# Mic_to_pi_entire_design_without_pinouts.net
KiCad netlist of a schematic drawn in EAGLE
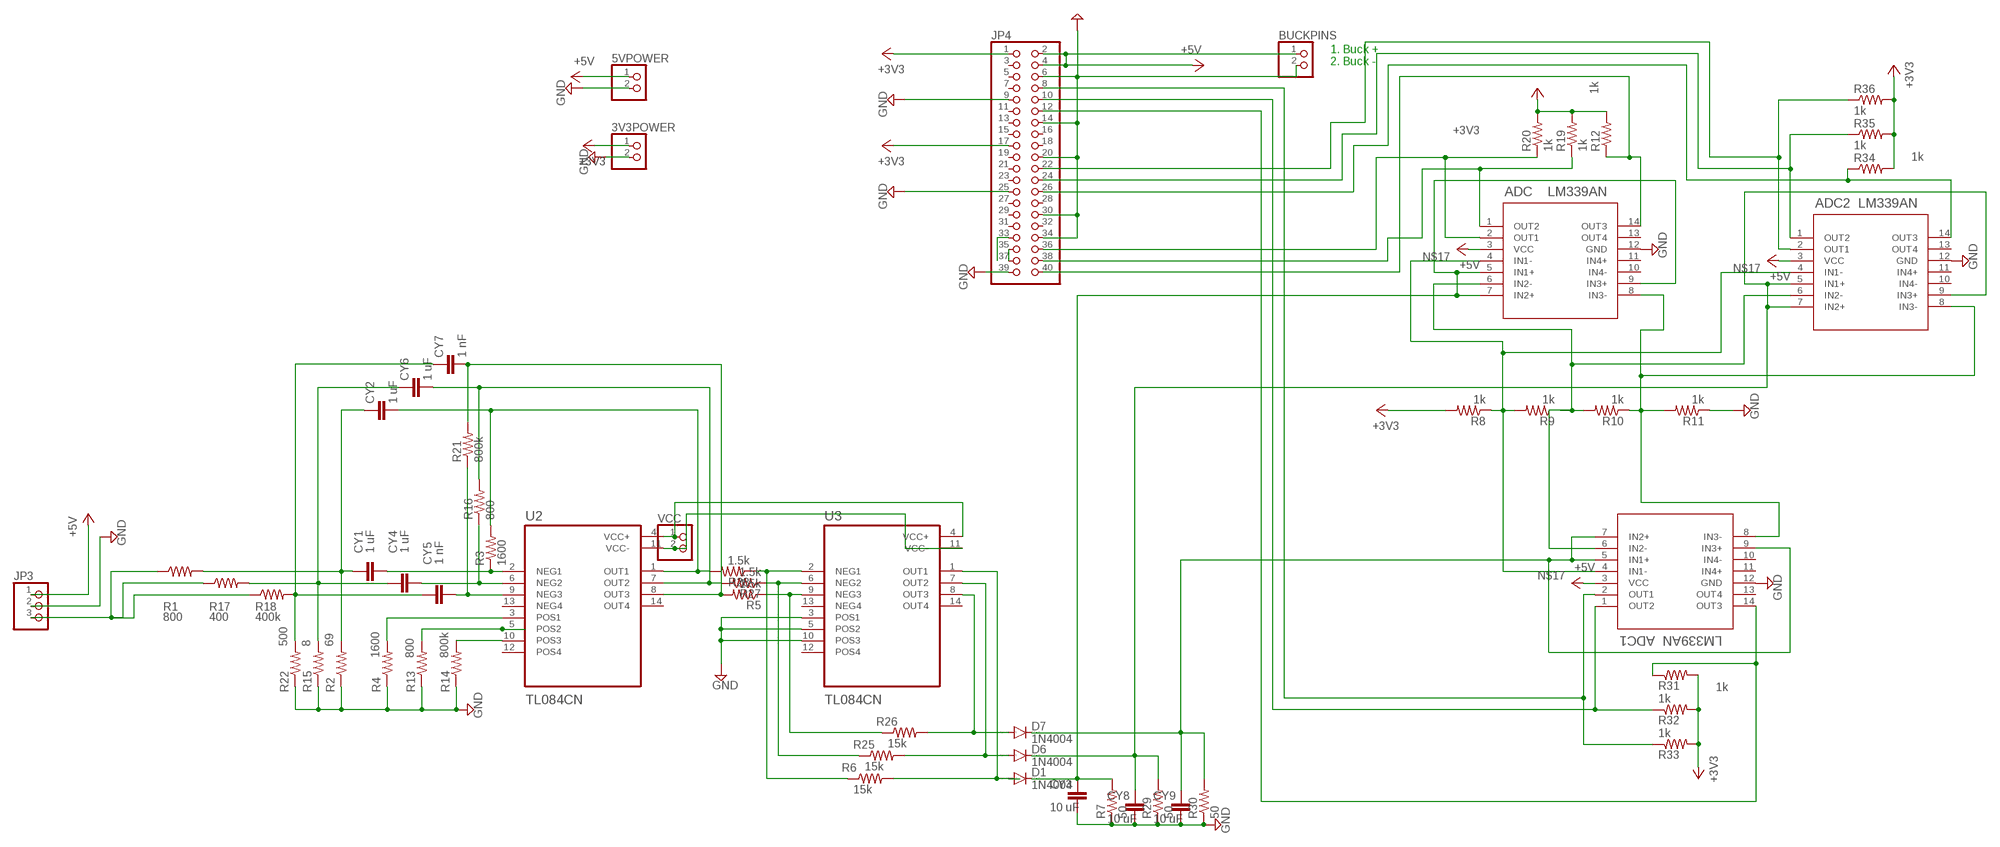
[diagram p0: schematic, sheet 1]

(export (version "E")
  (design (tool "Eeschema 10.0.6"))
  (components
    (comp (ref "3V3POWER")
      (value "PINHD-1X2")
      (footprint "eagle-import:1X02")
      (libsource (lib "eagle-import") (part "PINHD-1X2"))
    )
    (comp (ref "5VPOWER")
      (value "PINHD-1X2")
      (footprint "eagle-import:1X02")
      (libsource (lib "eagle-import") (part "PINHD-1X2"))
    )
    (comp (ref "ADC")
      (value "LM339AN")
      (footprint "eagle-import:PDIP14_646-06_ONS")
      (fields (field (name "COPYRIGHT") "Copyright (C) 2022 Ultra Librarian. All rights reserved."))
      (libsource (lib "eagle-import") (part "LM339AN"))
    )
    (comp (ref "ADC1")
      (value "LM339AN")
      (footprint "eagle-import:PDIP14_646-06_ONS")
      (fields (field (name "COPYRIGHT") "Copyright (C) 2022 Ultra Librarian. All rights reserved."))
      (libsource (lib "eagle-import") (part "LM339AN"))
    )
    (comp (ref "ADC2")
      (value "LM339AN")
      (footprint "eagle-import:PDIP14_646-06_ONS")
      (fields (field (name "COPYRIGHT") "Copyright (C) 2022 Ultra Librarian. All rights reserved."))
      (libsource (lib "eagle-import") (part "LM339AN"))
    )
    (comp (ref "BUCKPINS")
      (value "PINHD-1X2")
      (footprint "eagle-import:1X02")
      (libsource (lib "eagle-import") (part "PINHD-1X2"))
    )
    (comp (ref "CY1")
      (value "1 uF")
      (footprint "eagle-import:YC7B5")
      (libsource (lib "eagle-import") (part "CYYC7B5"))
    )
    (comp (ref "CY2")
      (value "1 uF")
      (footprint "eagle-import:YC7B5")
      (libsource (lib "eagle-import") (part "CYYC7B5"))
    )
    (comp (ref "CY3")
      (value "10 uF")
      (footprint "eagle-import:YC7B5")
      (libsource (lib "eagle-import") (part "CYYC7B5"))
    )
    (comp (ref "CY4")
      (value "1 uF")
      (footprint "eagle-import:YC7B5")
      (libsource (lib "eagle-import") (part "CYYC7B5"))
    )
    (comp (ref "CY5")
      (value "1 nF")
      (footprint "eagle-import:YC7B5")
      (libsource (lib "eagle-import") (part "CYYC7B5"))
    )
    (comp (ref "CY6")
      (value "1 uF")
      (footprint "eagle-import:YC7B5")
      (libsource (lib "eagle-import") (part "CYYC7B5"))
    )
    (comp (ref "CY7")
      (value "1 nF")
      (footprint "eagle-import:YC7B5")
      (libsource (lib "eagle-import") (part "CYYC7B5"))
    )
    (comp (ref "CY8")
      (value "10 uF")
      (footprint "eagle-import:YC7B5")
      (libsource (lib "eagle-import") (part "CYYC7B5"))
    )
    (comp (ref "CY9")
      (value "10 uF")
      (footprint "eagle-import:YC7B5")
      (libsource (lib "eagle-import") (part "CYYC7B5"))
    )
    (comp (ref "D1")
      (value "1N4004")
      (footprint "eagle-import:DO41-10")
      (libsource (lib "eagle-import") (part "1N4004"))
    )
    (comp (ref "D6")
      (value "1N4004")
      (footprint "eagle-import:DO41-10")
      (libsource (lib "eagle-import") (part "1N4004"))
    )
    (comp (ref "D7")
      (value "1N4004")
      (footprint "eagle-import:DO41-10")
      (libsource (lib "eagle-import") (part "1N4004"))
    )
    (comp (ref "JP3")
      (value "PINHD-1X3")
      (footprint "eagle-import:1X03")
      (libsource (lib "eagle-import") (part "PINHD-1X3"))
    )
    (comp (ref "JP4")
      (value "PINHD-2X20")
      (footprint "eagle-import:2X20")
      (libsource (lib "eagle-import") (part "PINHD-2X20"))
    )
    (comp (ref "R1")
      (value "800")
      (footprint "eagle-import:0204_7")
      (libsource (lib "eagle-import") (part "R-US_0204/7"))
    )
    (comp (ref "R2")
      (value "69")
      (footprint "eagle-import:0204_7")
      (libsource (lib "eagle-import") (part "R-US_0204/7"))
    )
    (comp (ref "R3")
      (value "1600")
      (footprint "eagle-import:0204_7")
      (libsource (lib "eagle-import") (part "R-US_0204/7"))
    )
    (comp (ref "R4")
      (value "1600")
      (footprint "eagle-import:0204_7")
      (libsource (lib "eagle-import") (part "R-US_0204/7"))
    )
    (comp (ref "R5")
      (value "1.5k")
      (footprint "eagle-import:0204_7")
      (libsource (lib "eagle-import") (part "R-US_0204/7"))
    )
    (comp (ref "R6")
      (value "15k")
      (footprint "eagle-import:0204_7")
      (libsource (lib "eagle-import") (part "R-US_0204/7"))
    )
    (comp (ref "R7")
      (value "50")
      (footprint "eagle-import:0204_7")
      (libsource (lib "eagle-import") (part "R-US_0204/7"))
    )
    (comp (ref "R8")
      (value "1k")
      (footprint "eagle-import:0204_7")
      (libsource (lib "eagle-import") (part "R-US_0204/7"))
    )
    (comp (ref "R9")
      (value "1k")
      (footprint "eagle-import:0207_2V")
      (libsource (lib "eagle-import") (part "R-US_0207/2V"))
    )
    (comp (ref "R10")
      (value "1k")
      (footprint "eagle-import:0207_2V")
      (libsource (lib "eagle-import") (part "R-US_0207/2V"))
    )
    (comp (ref "R11")
      (value "1k")
      (footprint "eagle-import:0207_2V")
      (libsource (lib "eagle-import") (part "R-US_0207/2V"))
    )
    (comp (ref "R12")
      (value "1k")
      (footprint "eagle-import:0207_2V")
      (libsource (lib "eagle-import") (part "R-US_0207/2V"))
    )
    (comp (ref "R13")
      (value "800")
      (footprint "eagle-import:0204_7")
      (libsource (lib "eagle-import") (part "R-US_0204/7"))
    )
    (comp (ref "R14")
      (value "800k")
      (footprint "eagle-import:0204_7")
      (libsource (lib "eagle-import") (part "R-US_0204/7"))
    )
    (comp (ref "R15")
      (value "8")
      (footprint "eagle-import:0204_7")
      (libsource (lib "eagle-import") (part "R-US_0204/7"))
    )
    (comp (ref "R16")
      (value "800")
      (footprint "eagle-import:0204_7")
      (libsource (lib "eagle-import") (part "R-US_0204/7"))
    )
    (comp (ref "R17")
      (value "400")
      (footprint "eagle-import:0204_7")
      (libsource (lib "eagle-import") (part "R-US_0204/7"))
    )
    (comp (ref "R18")
      (value "400k")
      (footprint "eagle-import:0204_7")
      (libsource (lib "eagle-import") (part "R-US_0204/7"))
    )
    (comp (ref "R19")
      (value "1k")
      (footprint "eagle-import:0204_7")
      (libsource (lib "eagle-import") (part "R-US_0204/7"))
    )
    (comp (ref "R20")
      (value "1k")
      (footprint "eagle-import:0204_7")
      (libsource (lib "eagle-import") (part "R-US_0204/7"))
    )
    (comp (ref "R21")
      (value "800k")
      (footprint "eagle-import:0204_7")
      (libsource (lib "eagle-import") (part "R-US_0204/7"))
    )
    (comp (ref "R22")
      (value "500")
      (footprint "eagle-import:0204_7")
      (libsource (lib "eagle-import") (part "R-US_0204/7"))
    )
    (comp (ref "R25")
      (value "15k")
      (footprint "eagle-import:0204_7")
      (libsource (lib "eagle-import") (part "R-US_0204/7"))
    )
    (comp (ref "R26")
      (value "15k")
      (footprint "eagle-import:0204_7")
      (libsource (lib "eagle-import") (part "R-US_0204/7"))
    )
    (comp (ref "R27")
      (value "1.5k")
      (footprint "eagle-import:0204_7")
      (libsource (lib "eagle-import") (part "R-US_0204/7"))
    )
    (comp (ref "R28")
      (value "1.5k")
      (footprint "eagle-import:0204_7")
      (libsource (lib "eagle-import") (part "R-US_0204/7"))
    )
    (comp (ref "R29")
      (value "50")
      (footprint "eagle-import:0204_7")
      (libsource (lib "eagle-import") (part "R-US_0204/7"))
    )
    (comp (ref "R30")
      (value "50")
      (footprint "eagle-import:0204_7")
      (libsource (lib "eagle-import") (part "R-US_0204/7"))
    )
    (comp (ref "R31")
      (value "1k")
      (footprint "eagle-import:0207_2V")
      (libsource (lib "eagle-import") (part "R-US_0207/2V"))
    )
    (comp (ref "R32")
      (value "1k")
      (footprint "eagle-import:0204_7")
      (libsource (lib "eagle-import") (part "R-US_0204/7"))
    )
    (comp (ref "R33")
      (value "1k")
      (footprint "eagle-import:0204_7")
      (libsource (lib "eagle-import") (part "R-US_0204/7"))
    )
    (comp (ref "R34")
      (value "1k")
      (footprint "eagle-import:0207_2V")
      (libsource (lib "eagle-import") (part "R-US_0207/2V"))
    )
    (comp (ref "R35")
      (value "1k")
      (footprint "eagle-import:0204_7")
      (libsource (lib "eagle-import") (part "R-US_0204/7"))
    )
    (comp (ref "R36")
      (value "1k")
      (footprint "eagle-import:0204_7")
      (libsource (lib "eagle-import") (part "R-US_0204/7"))
    )
    (comp (ref "U2")
      (value "TL084CN")
      (footprint "eagle-import:DIP794W45P254L1969H508Q14")
      (fields (field (name "DIGI-KEY_PART_NUMBER") "296-1784-5-ND") (field (name "MF") "Texas Instruments"))
      (libsource (lib "eagle-import") (part "TL084CN"))
    )
    (comp (ref "U3")
      (value "TL084CN")
      (footprint "eagle-import:DIP794W45P254L1969H508Q14")
      (fields (field (name "DIGI-KEY_PART_NUMBER") "296-1784-5-ND") (field (name "MF") "Texas Instruments"))
      (libsource (lib "eagle-import") (part "TL084CN"))
    )
    (comp (ref "VCC")
      (value "PINHD-1X2")
      (footprint "eagle-import:1X02")
      (libsource (lib "eagle-import") (part "PINHD-1X2"))
    )
  )
  (nets
    (net (code "1") (name "+3V3") (class "Default")
      (node (ref "3V3POWER") (pin "1") (pinfunction "1_1") (pintype "passive"))
      (node (ref "JP4") (pin "1") (pinfunction "1_1") (pintype "passive"))
      (node (ref "JP4") (pin "17") (pinfunction "17_17") (pintype "passive"))
      (node (ref "R12") (pin "2") (pinfunction "2_2") (pintype "passive"))
      (node (ref "R19") (pin "2") (pinfunction "2_2") (pintype "passive"))
      (node (ref "R20") (pin "2") (pinfunction "2_2") (pintype "passive"))
      (node (ref "R31") (pin "2") (pinfunction "2_2") (pintype "passive"))
      (node (ref "R32") (pin "2") (pinfunction "2_2") (pintype "passive"))
      (node (ref "R33") (pin "2") (pinfunction "2_2") (pintype "passive"))
      (node (ref "R34") (pin "2") (pinfunction "2_2") (pintype "passive"))
      (node (ref "R35") (pin "2") (pinfunction "2_2") (pintype "passive"))
      (node (ref "R36") (pin "2") (pinfunction "2_2") (pintype "passive"))
      (node (ref "R8") (pin "2") (pinfunction "2_2") (pintype "passive"))
    )
    (net (code "2") (name "+5V") (class "Default")
      (node (ref "5VPOWER") (pin "1") (pinfunction "1_1") (pintype "passive"))
      (node (ref "ADC") (pin "3") (pinfunction "VCC_3") (pintype "power_in"))
      (node (ref "ADC1") (pin "3") (pinfunction "VCC_3") (pintype "power_in"))
      (node (ref "ADC2") (pin "3") (pinfunction "VCC_3") (pintype "power_in"))
      (node (ref "BUCKPINS") (pin "1") (pinfunction "1_1") (pintype "passive"))
      (node (ref "JP3") (pin "1") (pinfunction "1_1") (pintype "passive"))
      (node (ref "JP4") (pin "2") (pinfunction "2_2") (pintype "passive"))
      (node (ref "JP4") (pin "4") (pinfunction "4_4") (pintype "passive"))
    )
    (net (code "3") (name "/N$17") (class "Default")
      (node (ref "ADC") (pin "4") (pinfunction "IN1-_4") (pintype "input"))
      (node (ref "ADC1") (pin "4") (pinfunction "IN1-_4") (pintype "input"))
      (node (ref "ADC2") (pin "4") (pinfunction "IN1-_4") (pintype "input"))
      (node (ref "R8") (pin "1") (pinfunction "1_1") (pintype "passive"))
      (node (ref "R9") (pin "2") (pinfunction "2_2") (pintype "passive"))
    )
    (net (code "4") (name "GND") (class "Default")
      (node (ref "3V3POWER") (pin "2") (pinfunction "2_2") (pintype "passive"))
      (node (ref "5VPOWER") (pin "2") (pinfunction "2_2") (pintype "passive"))
      (node (ref "ADC") (pin "12") (pinfunction "GND_12") (pintype "passive"))
      (node (ref "ADC1") (pin "12") (pinfunction "GND_12") (pintype "passive"))
      (node (ref "ADC2") (pin "12") (pinfunction "GND_12") (pintype "passive"))
      (node (ref "BUCKPINS") (pin "2") (pinfunction "2_2") (pintype "passive"))
      (node (ref "CY3") (pin "2") (pinfunction "2_2") (pintype "passive"))
      (node (ref "CY8") (pin "2") (pinfunction "2_2") (pintype "passive"))
      (node (ref "CY9") (pin "2") (pinfunction "2_2") (pintype "passive"))
      (node (ref "JP3") (pin "2") (pinfunction "2_2") (pintype "passive"))
      (node (ref "JP4") (pin "14") (pinfunction "14_14") (pintype "passive"))
      (node (ref "JP4") (pin "20") (pinfunction "20_20") (pintype "passive"))
      (node (ref "JP4") (pin "25") (pinfunction "25_25") (pintype "passive"))
      (node (ref "JP4") (pin "30") (pinfunction "30_30") (pintype "passive"))
      (node (ref "JP4") (pin "34") (pinfunction "34_34") (pintype "passive"))
      (node (ref "JP4") (pin "39") (pinfunction "39_39") (pintype "passive"))
      (node (ref "JP4") (pin "6") (pinfunction "6_6") (pintype "passive"))
      (node (ref "JP4") (pin "9") (pinfunction "9_9") (pintype "passive"))
      (node (ref "R11") (pin "1") (pinfunction "1_1") (pintype "passive"))
      (node (ref "R13") (pin "1") (pinfunction "1_1") (pintype "passive"))
      (node (ref "R14") (pin "1") (pinfunction "1_1") (pintype "passive"))
      (node (ref "R15") (pin "1") (pinfunction "1_1") (pintype "passive"))
      (node (ref "R2") (pin "1") (pinfunction "1_1") (pintype "passive"))
      (node (ref "R22") (pin "1") (pinfunction "1_1") (pintype "passive"))
      (node (ref "R29") (pin "1") (pinfunction "1_1") (pintype "passive"))
      (node (ref "R30") (pin "1") (pinfunction "1_1") (pintype "passive"))
      (node (ref "R4") (pin "1") (pinfunction "1_1") (pintype "passive"))
      (node (ref "R7") (pin "1") (pinfunction "1_1") (pintype "passive"))
      (node (ref "U3") (pin "10") (pinfunction "POS3_10") (pintype "input"))
      (node (ref "U3") (pin "3") (pinfunction "POS1_3") (pintype "input"))
      (node (ref "U3") (pin "5") (pinfunction "POS2_5") (pintype "input"))
    )
    (net (code "5") (name "Net-(ADC-IN1+)") (class "Default")
      (node (ref "ADC") (pin "5") (pinfunction "IN1+_5") (pintype "input"))
      (node (ref "ADC") (pin "7") (pinfunction "IN2+_7") (pintype "input"))
      (node (ref "ADC") (pin "9") (pinfunction "IN3+_9") (pintype "input"))
      (node (ref "CY3") (pin "1") (pinfunction "1_1") (pintype "passive"))
      (node (ref "D1") (pin "C") (pinfunction "C_C") (pintype "passive"))
      (node (ref "R7") (pin "2") (pinfunction "2_2") (pintype "passive"))
    )
    (net (code "6") (name "Net-(ADC-IN2-)") (class "Default")
      (node (ref "ADC") (pin "6") (pinfunction "IN2-_6") (pintype "input"))
      (node (ref "ADC1") (pin "6") (pinfunction "IN2-_6") (pintype "input"))
      (node (ref "ADC2") (pin "6") (pinfunction "IN2-_6") (pintype "input"))
      (node (ref "R10") (pin "2") (pinfunction "2_2") (pintype "passive"))
      (node (ref "R9") (pin "1") (pinfunction "1_1") (pintype "passive"))
    )
    (net (code "7") (name "Net-(ADC-IN3-)") (class "Default")
      (node (ref "ADC") (pin "8") (pinfunction "IN3-_8") (pintype "input"))
      (node (ref "ADC1") (pin "8") (pinfunction "IN3-_8") (pintype "input"))
      (node (ref "ADC2") (pin "8") (pinfunction "IN3-_8") (pintype "input"))
      (node (ref "R10") (pin "1") (pinfunction "1_1") (pintype "passive"))
      (node (ref "R11") (pin "2") (pinfunction "2_2") (pintype "passive"))
    )
    (net (code "8") (name "Net-(ADC-OUT1)") (class "Default")
      (node (ref "ADC") (pin "2") (pinfunction "OUT1_2") (pintype "output"))
      (node (ref "JP4") (pin "36") (pinfunction "36_36") (pintype "passive"))
      (node (ref "R20") (pin "1") (pinfunction "1_1") (pintype "passive"))
    )
    (net (code "9") (name "Net-(ADC-OUT2)") (class "Default")
      (node (ref "ADC") (pin "1") (pinfunction "OUT2_1") (pintype "output"))
      (node (ref "JP4") (pin "38") (pinfunction "38_38") (pintype "passive"))
      (node (ref "R19") (pin "1") (pinfunction "1_1") (pintype "passive"))
    )
    (net (code "10") (name "Net-(ADC-OUT3)") (class "Default")
      (node (ref "ADC") (pin "14") (pinfunction "OUT3_14") (pintype "output"))
      (node (ref "JP4") (pin "40") (pinfunction "40_40") (pintype "passive"))
      (node (ref "R12") (pin "1") (pinfunction "1_1") (pintype "passive"))
    )
    (net (code "11") (name "Net-(ADC1-IN1+)") (class "Default")
      (node (ref "ADC1") (pin "5") (pinfunction "IN1+_5") (pintype "input"))
      (node (ref "ADC1") (pin "7") (pinfunction "IN2+_7") (pintype "input"))
      (node (ref "ADC1") (pin "9") (pinfunction "IN3+_9") (pintype "input"))
      (node (ref "CY9") (pin "1") (pinfunction "1_1") (pintype "passive"))
      (node (ref "D7") (pin "C") (pinfunction "C_C") (pintype "passive"))
      (node (ref "R30") (pin "2") (pinfunction "2_2") (pintype "passive"))
    )
    (net (code "12") (name "Net-(ADC1-OUT1)") (class "Default")
      (node (ref "ADC1") (pin "2") (pinfunction "OUT1_2") (pintype "output"))
      (node (ref "JP4") (pin "8") (pinfunction "8_8") (pintype "passive"))
      (node (ref "R33") (pin "1") (pinfunction "1_1") (pintype "passive"))
    )
    (net (code "13") (name "Net-(ADC1-OUT2)") (class "Default")
      (node (ref "ADC1") (pin "1") (pinfunction "OUT2_1") (pintype "output"))
      (node (ref "JP4") (pin "10") (pinfunction "10_10") (pintype "passive"))
      (node (ref "R32") (pin "1") (pinfunction "1_1") (pintype "passive"))
    )
    (net (code "14") (name "Net-(ADC1-OUT3)") (class "Default")
      (node (ref "ADC1") (pin "14") (pinfunction "OUT3_14") (pintype "output"))
      (node (ref "JP4") (pin "12") (pinfunction "12_12") (pintype "passive"))
      (node (ref "R31") (pin "1") (pinfunction "1_1") (pintype "passive"))
    )
    (net (code "15") (name "Net-(ADC2-IN1+)") (class "Default")
      (node (ref "ADC2") (pin "5") (pinfunction "IN1+_5") (pintype "input"))
      (node (ref "ADC2") (pin "7") (pinfunction "IN2+_7") (pintype "input"))
      (node (ref "ADC2") (pin "9") (pinfunction "IN3+_9") (pintype "input"))
      (node (ref "CY8") (pin "1") (pinfunction "1_1") (pintype "passive"))
      (node (ref "D6") (pin "C") (pinfunction "C_C") (pintype "passive"))
      (node (ref "R29") (pin "2") (pinfunction "2_2") (pintype "passive"))
    )
    (net (code "16") (name "Net-(ADC2-OUT1)") (class "Default")
      (node (ref "ADC2") (pin "2") (pinfunction "OUT1_2") (pintype "output"))
      (node (ref "JP4") (pin "22") (pinfunction "22_22") (pintype "passive"))
      (node (ref "R36") (pin "1") (pinfunction "1_1") (pintype "passive"))
    )
    (net (code "17") (name "Net-(ADC2-OUT2)") (class "Default")
      (node (ref "ADC2") (pin "1") (pinfunction "OUT2_1") (pintype "output"))
      (node (ref "JP4") (pin "24") (pinfunction "24_24") (pintype "passive"))
      (node (ref "R35") (pin "1") (pinfunction "1_1") (pintype "passive"))
    )
    (net (code "18") (name "Net-(ADC2-OUT3)") (class "Default")
      (node (ref "ADC2") (pin "14") (pinfunction "OUT3_14") (pintype "output"))
      (node (ref "JP4") (pin "26") (pinfunction "26_26") (pintype "passive"))
      (node (ref "R34") (pin "1") (pinfunction "1_1") (pintype "passive"))
    )
    (net (code "19") (name "Net-(CY1-Pad1)") (class "Default")
      (node (ref "CY1") (pin "1") (pinfunction "1_1") (pintype "passive"))
      (node (ref "CY2") (pin "1") (pinfunction "1_1") (pintype "passive"))
      (node (ref "R1") (pin "2") (pinfunction "2_2") (pintype "passive"))
      (node (ref "R2") (pin "2") (pinfunction "2_2") (pintype "passive"))
    )
    (net (code "20") (name "Net-(CY4-Pad1)") (class "Default")
      (node (ref "CY4") (pin "1") (pinfunction "1_1") (pintype "passive"))
      (node (ref "CY6") (pin "1") (pinfunction "1_1") (pintype "passive"))
      (node (ref "R15") (pin "2") (pinfunction "2_2") (pintype "passive"))
      (node (ref "R17") (pin "2") (pinfunction "2_2") (pintype "passive"))
    )
    (net (code "21") (name "Net-(CY5-Pad1)") (class "Default")
      (node (ref "CY5") (pin "1") (pinfunction "1_1") (pintype "passive"))
      (node (ref "CY7") (pin "1") (pinfunction "1_1") (pintype "passive"))
      (node (ref "R18") (pin "2") (pinfunction "2_2") (pintype "passive"))
      (node (ref "R22") (pin "2") (pinfunction "2_2") (pintype "passive"))
    )
    (net (code "22") (name "Net-(JP3-Pad3)") (class "Default")
      (node (ref "JP3") (pin "3") (pinfunction "3_3") (pintype "passive"))
      (node (ref "R1") (pin "1") (pinfunction "1_1") (pintype "passive"))
      (node (ref "R17") (pin "1") (pinfunction "1_1") (pintype "passive"))
      (node (ref "R18") (pin "1") (pinfunction "1_1") (pintype "passive"))
    )
    (net (code "23") (name "Net-(JP4-Pad35)") (class "Default")
      (node (ref "JP4") (pin "35") (pinfunction "35_35") (pintype "passive"))
      (node (ref "JP4") (pin "37") (pinfunction "37_37") (pintype "passive"))
    )
    (net (code "24") (name "Net-(U2-NEG1)") (class "Default")
      (node (ref "CY1") (pin "2") (pinfunction "2_2") (pintype "passive"))
      (node (ref "R3") (pin "1") (pinfunction "1_1") (pintype "passive"))
      (node (ref "U2") (pin "2") (pinfunction "NEG1_2") (pintype "input"))
    )
    (net (code "25") (name "Net-(U2-NEG2)") (class "Default")
      (node (ref "CY4") (pin "2") (pinfunction "2_2") (pintype "passive"))
      (node (ref "R16") (pin "1") (pinfunction "1_1") (pintype "passive"))
      (node (ref "U2") (pin "6") (pinfunction "NEG2_6") (pintype "input"))
    )
    (net (code "26") (name "Net-(U2-NEG3)") (class "Default")
      (node (ref "CY5") (pin "2") (pinfunction "2_2") (pintype "passive"))
      (node (ref "R21") (pin "1") (pinfunction "1_1") (pintype "passive"))
      (node (ref "U2") (pin "9") (pinfunction "NEG3_9") (pintype "input"))
    )
    (net (code "27") (name "Net-(U2-OUT1)") (class "Default")
      (node (ref "CY2") (pin "2") (pinfunction "2_2") (pintype "passive"))
      (node (ref "R28") (pin "2") (pinfunction "2_2") (pintype "passive"))
      (node (ref "R3") (pin "2") (pinfunction "2_2") (pintype "passive"))
      (node (ref "U2") (pin "1") (pinfunction "OUT1_1") (pintype "output"))
    )
    (net (code "28") (name "Net-(U2-OUT2)") (class "Default")
      (node (ref "CY6") (pin "2") (pinfunction "2_2") (pintype "passive"))
      (node (ref "R16") (pin "2") (pinfunction "2_2") (pintype "passive"))
      (node (ref "R27") (pin "2") (pinfunction "2_2") (pintype "passive"))
      (node (ref "U2") (pin "7") (pinfunction "OUT2_7") (pintype "output"))
    )
    (net (code "29") (name "Net-(U2-OUT3)") (class "Default")
      (node (ref "CY7") (pin "2") (pinfunction "2_2") (pintype "passive"))
      (node (ref "R21") (pin "2") (pinfunction "2_2") (pintype "passive"))
      (node (ref "R5") (pin "2") (pinfunction "2_2") (pintype "passive"))
      (node (ref "U2") (pin "8") (pinfunction "OUT3_8") (pintype "output"))
    )
    (net (code "30") (name "Net-(U2-POS1)") (class "Default")
      (node (ref "R4") (pin "2") (pinfunction "2_2") (pintype "passive"))
      (node (ref "U2") (pin "3") (pinfunction "POS1_3") (pintype "input"))
    )
    (net (code "31") (name "Net-(U2-POS2)") (class "Default")
      (node (ref "R13") (pin "2") (pinfunction "2_2") (pintype "passive"))
      (node (ref "U2") (pin "5") (pinfunction "POS2_5") (pintype "input"))
    )
    (net (code "32") (name "Net-(U2-POS3)") (class "Default")
      (node (ref "R14") (pin "2") (pinfunction "2_2") (pintype "passive"))
      (node (ref "U2") (pin "10") (pinfunction "POS3_10") (pintype "input"))
    )
    (net (code "33") (name "Net-(U2-VCC+)") (class "Default")
      (node (ref "U2") (pin "4") (pinfunction "VCC+_4") (pintype "power_in"))
      (node (ref "U3") (pin "4") (pinfunction "VCC+_4") (pintype "power_in"))
      (node (ref "VCC") (pin "1") (pinfunction "1_1") (pintype "passive"))
    )
    (net (code "34") (name "Net-(U2-VCC-)") (class "Default")
      (node (ref "U2") (pin "11") (pinfunction "VCC-_11") (pintype "power_in"))
      (node (ref "U3") (pin "11") (pinfunction "VCC-_11") (pintype "power_in"))
      (node (ref "VCC") (pin "2") (pinfunction "2_2") (pintype "passive"))
    )
    (net (code "35") (name "Net-(U3-NEG1)") (class "Default")
      (node (ref "R28") (pin "1") (pinfunction "1_1") (pintype "passive"))
      (node (ref "R6") (pin "1") (pinfunction "1_1") (pintype "passive"))
      (node (ref "U3") (pin "2") (pinfunction "NEG1_2") (pintype "input"))
    )
    (net (code "36") (name "Net-(U3-NEG2)") (class "Default")
      (node (ref "R25") (pin "1") (pinfunction "1_1") (pintype "passive"))
      (node (ref "R27") (pin "1") (pinfunction "1_1") (pintype "passive"))
      (node (ref "U3") (pin "6") (pinfunction "NEG2_6") (pintype "input"))
    )
    (net (code "37") (name "Net-(U3-NEG3)") (class "Default")
      (node (ref "R26") (pin "1") (pinfunction "1_1") (pintype "passive"))
      (node (ref "R5") (pin "1") (pinfunction "1_1") (pintype "passive"))
      (node (ref "U3") (pin "9") (pinfunction "NEG3_9") (pintype "input"))
    )
    (net (code "38") (name "Net-(U3-OUT1)") (class "Default")
      (node (ref "D1") (pin "A") (pinfunction "A_A") (pintype "passive"))
      (node (ref "R6") (pin "2") (pinfunction "2_2") (pintype "passive"))
      (node (ref "U3") (pin "1") (pinfunction "OUT1_1") (pintype "output"))
    )
    (net (code "39") (name "Net-(U3-OUT2)") (class "Default")
      (node (ref "D6") (pin "A") (pinfunction "A_A") (pintype "passive"))
      (node (ref "R25") (pin "2") (pinfunction "2_2") (pintype "passive"))
      (node (ref "U3") (pin "7") (pinfunction "OUT2_7") (pintype "output"))
    )
    (net (code "40") (name "Net-(U3-OUT3)") (class "Default")
      (node (ref "D7") (pin "A") (pinfunction "A_A") (pintype "passive"))
      (node (ref "R26") (pin "2") (pinfunction "2_2") (pintype "passive"))
      (node (ref "U3") (pin "8") (pinfunction "OUT3_8") (pintype "output"))
    )
    (net (code "41") (name "unconnected-(ADC-IN4+-Pad11)") (class "Default")
      (node (ref "ADC") (pin "11") (pinfunction "IN4+_11") (pintype "input"))
    )
    (net (code "42") (name "unconnected-(ADC-IN4--Pad10)") (class "Default")
      (node (ref "ADC") (pin "10") (pinfunction "IN4-_10") (pintype "input"))
    )
    (net (code "43") (name "unconnected-(ADC-OUT4-Pad13)") (class "Default")
      (node (ref "ADC") (pin "13") (pinfunction "OUT4_13") (pintype "output"))
    )
    (net (code "44") (name "unconnected-(ADC1-IN4+-Pad11)") (class "Default")
      (node (ref "ADC1") (pin "11") (pinfunction "IN4+_11") (pintype "input"))
    )
    (net (code "45") (name "unconnected-(ADC1-IN4--Pad10)") (class "Default")
      (node (ref "ADC1") (pin "10") (pinfunction "IN4-_10") (pintype "input"))
    )
    (net (code "46") (name "unconnected-(ADC1-OUT4-Pad13)") (class "Default")
      (node (ref "ADC1") (pin "13") (pinfunction "OUT4_13") (pintype "output"))
    )
    (net (code "47") (name "unconnected-(ADC2-IN4+-Pad11)") (class "Default")
      (node (ref "ADC2") (pin "11") (pinfunction "IN4+_11") (pintype "input"))
    )
    (net (code "48") (name "unconnected-(ADC2-IN4--Pad10)") (class "Default")
      (node (ref "ADC2") (pin "10") (pinfunction "IN4-_10") (pintype "input"))
    )
    (net (code "49") (name "unconnected-(ADC2-OUT4-Pad13)") (class "Default")
      (node (ref "ADC2") (pin "13") (pinfunction "OUT4_13") (pintype "output"))
    )
    (net (code "50") (name "unconnected-(JP4-Pad3)") (class "Default")
      (node (ref "JP4") (pin "3") (pinfunction "3_3") (pintype "passive"))
    )
    (net (code "51") (name "unconnected-(JP4-Pad5)") (class "Default")
      (node (ref "JP4") (pin "5") (pinfunction "5_5") (pintype "passive"))
    )
    (net (code "52") (name "unconnected-(JP4-Pad7)") (class "Default")
      (node (ref "JP4") (pin "7") (pinfunction "7_7") (pintype "passive"))
    )
    (net (code "53") (name "unconnected-(JP4-Pad11)") (class "Default")
      (node (ref "JP4") (pin "11") (pinfunction "11_11") (pintype "passive"))
    )
    (net (code "54") (name "unconnected-(JP4-Pad13)") (class "Default")
      (node (ref "JP4") (pin "13") (pinfunction "13_13") (pintype "passive"))
    )
    (net (code "55") (name "unconnected-(JP4-Pad15)") (class "Default")
      (node (ref "JP4") (pin "15") (pinfunction "15_15") (pintype "passive"))
    )
    (net (code "56") (name "unconnected-(JP4-Pad16)") (class "Default")
      (node (ref "JP4") (pin "16") (pinfunction "16_16") (pintype "passive"))
    )
    (net (code "57") (name "unconnected-(JP4-Pad18)") (class "Default")
      (node (ref "JP4") (pin "18") (pinfunction "18_18") (pintype "passive"))
    )
    (net (code "58") (name "unconnected-(JP4-Pad19)") (class "Default")
      (node (ref "JP4") (pin "19") (pinfunction "19_19") (pintype "passive"))
    )
    (net (code "59") (name "unconnected-(JP4-Pad21)") (class "Default")
      (node (ref "JP4") (pin "21") (pinfunction "21_21") (pintype "passive"))
    )
    (net (code "60") (name "unconnected-(JP4-Pad23)") (class "Default")
      (node (ref "JP4") (pin "23") (pinfunction "23_23") (pintype "passive"))
    )
    (net (code "61") (name "unconnected-(JP4-Pad27)") (class "Default")
      (node (ref "JP4") (pin "27") (pinfunction "27_27") (pintype "passive"))
    )
    (net (code "62") (name "unconnected-(JP4-Pad28)") (class "Default")
      (node (ref "JP4") (pin "28") (pinfunction "28_28") (pintype "passive"))
    )
    (net (code "63") (name "unconnected-(JP4-Pad29)") (class "Default")
      (node (ref "JP4") (pin "29") (pinfunction "29_29") (pintype "passive"))
    )
    (net (code "64") (name "unconnected-(JP4-Pad31)") (class "Default")
      (node (ref "JP4") (pin "31") (pinfunction "31_31") (pintype "passive"))
    )
    (net (code "65") (name "unconnected-(JP4-Pad32)") (class "Default")
      (node (ref "JP4") (pin "32") (pinfunction "32_32") (pintype "passive"))
    )
    (net (code "66") (name "unconnected-(JP4-Pad33)") (class "Default")
      (node (ref "JP4") (pin "33") (pinfunction "33_33") (pintype "passive"))
    )
    (net (code "67") (name "unconnected-(U2-NEG4-Pad13)") (class "Default")
      (node (ref "U2") (pin "13") (pinfunction "NEG4_13") (pintype "input"))
    )
    (net (code "68") (name "unconnected-(U2-OUT4-Pad14)") (class "Default")
      (node (ref "U2") (pin "14") (pinfunction "OUT4_14") (pintype "output"))
    )
    (net (code "69") (name "unconnected-(U2-POS4-Pad12)") (class "Default")
      (node (ref "U2") (pin "12") (pinfunction "POS4_12") (pintype "input"))
    )
    (net (code "70") (name "unconnected-(U3-NEG4-Pad13)") (class "Default")
      (node (ref "U3") (pin "13") (pinfunction "NEG4_13") (pintype "input"))
    )
    (net (code "71") (name "unconnected-(U3-OUT4-Pad14)") (class "Default")
      (node (ref "U3") (pin "14") (pinfunction "OUT4_14") (pintype "output"))
    )
    (net (code "72") (name "unconnected-(U3-POS4-Pad12)") (class "Default")
      (node (ref "U3") (pin "12") (pinfunction "POS4_12") (pintype "input"))
    )
  )
)
